# 2_0.net
KiCad netlist of a schematic drawn in Altium Designer
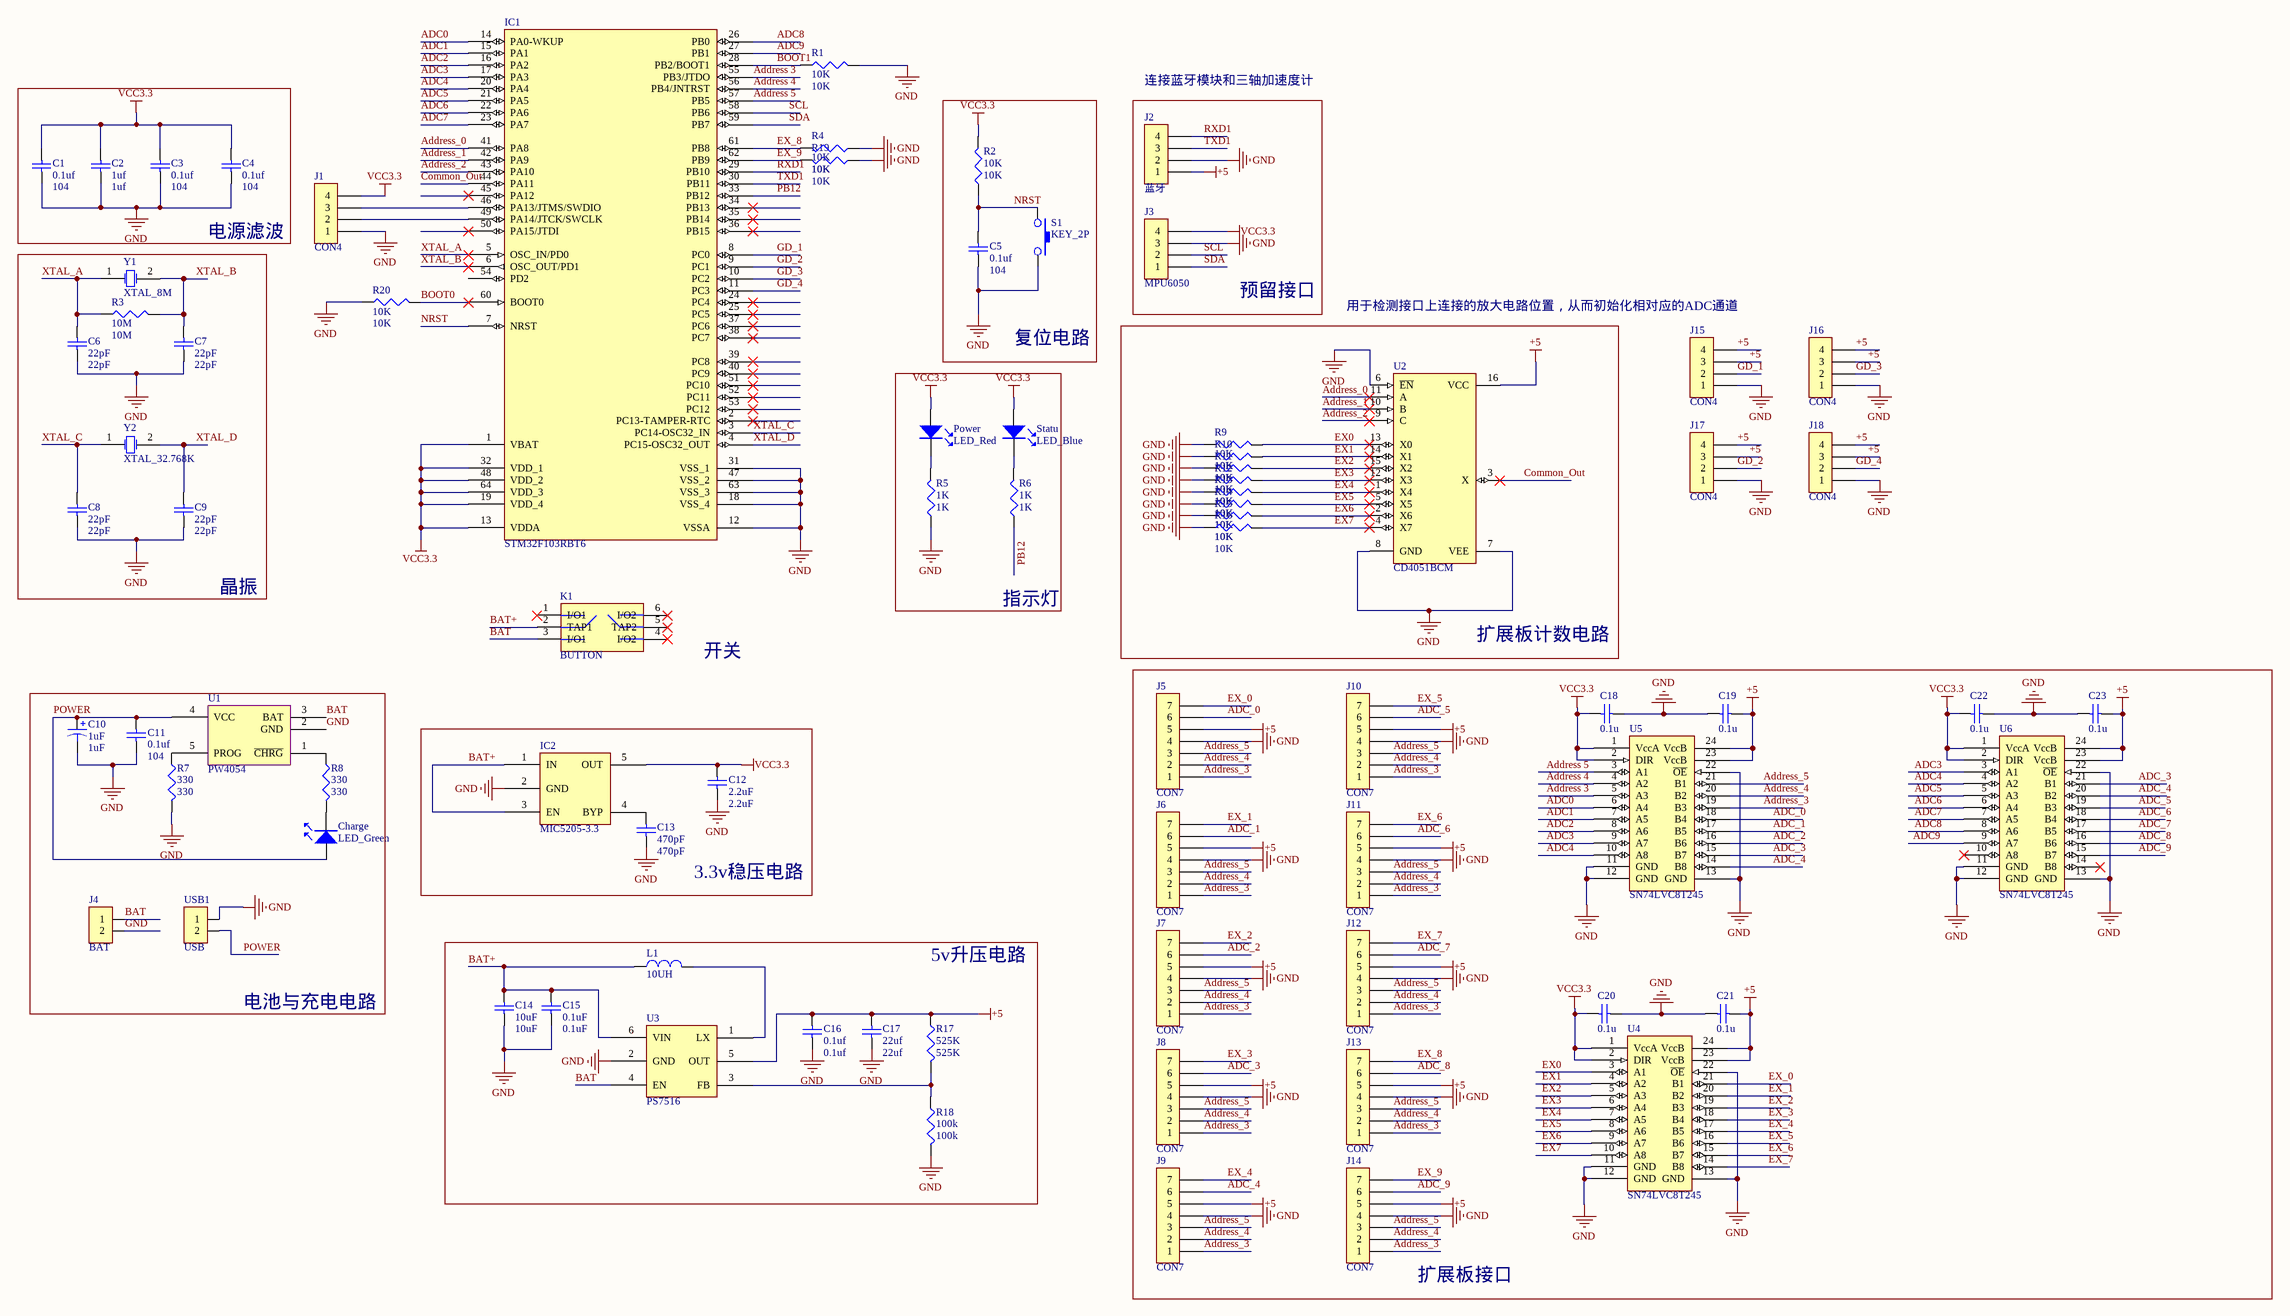
[diagram p0: 主控板原理图2.0.SchDoc]

(export (version "E")
  (design (tool "Eeschema 10.0.6"))
  (components
    (comp (ref "C1")
      (value "0.1uf")
      (footprint "6-0805_L")
      (description "Capacitor (Semiconductor SIM Model)")
      (fields (field (name "ALTIUM_VALUE") "104") (field (name "PUBLISHER") "Altium Limited"))
      (libsource (lib "Miscellaneous Devices") (part "Cap Semi"))
    )
    (comp (ref "C2")
      (value "1uf")
      (footprint "6-0805_L")
      (description "Capacitor (Semiconductor SIM Model)")
      (fields (field (name "ALTIUM_VALUE") "1uf") (field (name "PUBLISHER") "Altium Limited"))
      (libsource (lib "Miscellaneous Devices") (part "Cap Semi"))
    )
    (comp (ref "C3")
      (value "0.1uf")
      (footprint "6-0805_L")
      (description "Capacitor (Semiconductor SIM Model)")
      (fields (field (name "ALTIUM_VALUE") "104") (field (name "PUBLISHER") "Altium Limited"))
      (libsource (lib "Miscellaneous Devices") (part "Cap Semi"))
    )
    (comp (ref "C4")
      (value "0.1uf")
      (footprint "6-0805_L")
      (description "Capacitor (Semiconductor SIM Model)")
      (fields (field (name "ALTIUM_VALUE") "104") (field (name "PUBLISHER") "Altium Limited"))
      (libsource (lib "Miscellaneous Devices") (part "Cap Semi"))
    )
    (comp (ref "C5")
      (value "0.1uf")
      (footprint "6-0805_L")
      (description "Capacitor (Semiconductor SIM Model)")
      (fields (field (name "ALTIUM_VALUE") "104") (field (name "PUBLISHER") "Altium Limited"))
      (libsource (lib "Miscellaneous Devices") (part "Cap Semi"))
    )
    (comp (ref "C6")
      (value "22pF")
      (footprint "6-0805_L")
      (description "Capacitor (Semiconductor SIM Model)")
      (fields (field (name "ALTIUM_VALUE") "22pF") (field (name "PUBLISHER") "Altium Limited"))
      (libsource (lib "Miscellaneous Devices") (part "Cap Semi"))
    )
    (comp (ref "C7")
      (value "22pF")
      (footprint "6-0805_L")
      (description "Capacitor (Semiconductor SIM Model)")
      (fields (field (name "ALTIUM_VALUE") "22pF") (field (name "PUBLISHER") "Altium Limited"))
      (libsource (lib "Miscellaneous Devices") (part "Cap Semi"))
    )
    (comp (ref "C8")
      (value "22pF")
      (footprint "6-0805_L")
      (description "Capacitor (Semiconductor SIM Model)")
      (fields (field (name "ALTIUM_VALUE") "22pF") (field (name "PUBLISHER") "Altium Limited"))
      (libsource (lib "Miscellaneous Devices") (part "Cap Semi"))
    )
    (comp (ref "C9")
      (value "22pF")
      (footprint "6-0805_L")
      (description "Capacitor (Semiconductor SIM Model)")
      (fields (field (name "ALTIUM_VALUE") "22pF") (field (name "PUBLISHER") "Altium Limited"))
      (libsource (lib "Miscellaneous Devices") (part "Cap Semi"))
    )
    (comp (ref "C10")
      (value "1uF")
      (footprint "C0805")
      (description "Polarized Capacitor (Surface Mount)")
      (fields (field (name "ALTIUM_VALUE") "1uF") (field (name "PUBLISHER") "Altium Limited"))
      (libsource (lib "Miscellaneous Devices") (part "Cap Pol3"))
    )
    (comp (ref "C11")
      (value "0.1uf")
      (footprint "6-0805_L")
      (description "Capacitor (Semiconductor SIM Model)")
      (fields (field (name "ALTIUM_VALUE") "104") (field (name "PUBLISHER") "Altium Limited"))
      (libsource (lib "Miscellaneous Devices") (part "Cap Semi"))
    )
    (comp (ref "C12")
      (value "2.2uF")
      (footprint "6-0805_L")
      (description "Capacitor (Semiconductor SIM Model)")
      (fields (field (name "ALTIUM_VALUE") "2.2uF") (field (name "PUBLISHER") "Altium Limited"))
      (libsource (lib "Miscellaneous Devices") (part "Cap Semi"))
    )
    (comp (ref "C13")
      (value "470pF")
      (footprint "6-0805_L")
      (description "Capacitor (Semiconductor SIM Model)")
      (fields (field (name "ALTIUM_VALUE") "470pF") (field (name "PUBLISHER") "Altium Limited"))
      (libsource (lib "Miscellaneous Devices") (part "Cap Semi"))
    )
    (comp (ref "C14")
      (value "10uF")
      (footprint "6-0805_L")
      (description "Capacitor (Semiconductor SIM Model)")
      (fields (field (name "ALTIUM_VALUE") "10uF") (field (name "PUBLISHER") "Altium Limited"))
      (libsource (lib "Miscellaneous Devices") (part "Cap Semi"))
    )
    (comp (ref "C15")
      (value "0.1uF")
      (footprint "6-0805_L")
      (description "Capacitor (Semiconductor SIM Model)")
      (fields (field (name "ALTIUM_VALUE") "0.1uF") (field (name "PUBLISHER") "Altium Limited"))
      (libsource (lib "Miscellaneous Devices") (part "Cap Semi"))
    )
    (comp (ref "C16")
      (value "0.1uf")
      (footprint "6-0805_L")
      (description "Capacitor (Semiconductor SIM Model)")
      (fields (field (name "ALTIUM_VALUE") "0.1uf") (field (name "PUBLISHER") "Altium Limited"))
      (libsource (lib "Miscellaneous Devices") (part "Cap Semi"))
    )
    (comp (ref "C17")
      (value "22uf")
      (footprint "6-0805_L")
      (description "Capacitor (Semiconductor SIM Model)")
      (fields (field (name "ALTIUM_VALUE") "22uf") (field (name "PUBLISHER") "Altium Limited"))
      (libsource (lib "Miscellaneous Devices") (part "Cap Semi"))
    )
    (comp (ref "C18")
      (value "0.1u")
      (footprint "CAP1608")
      (description "Capacitor")
      (fields (field (name "Comment") "Cap") (field (name "PUBLISHER") "Altium Limited"))
      (libsource (lib "Miscellaneous Devices") (part "Cap"))
    )
    (comp (ref "C19")
      (value "0.1u")
      (footprint "CAP1608")
      (description "Capacitor")
      (fields (field (name "Comment") "Cap") (field (name "PUBLISHER") "Altium Limited"))
      (libsource (lib "Miscellaneous Devices") (part "Cap"))
    )
    (comp (ref "C20")
      (value "0.1u")
      (footprint "CAP1608")
      (description "Capacitor")
      (fields (field (name "Comment") "Cap") (field (name "PUBLISHER") "Altium Limited"))
      (libsource (lib "Miscellaneous Devices") (part "Cap"))
    )
    (comp (ref "C21")
      (value "0.1u")
      (footprint "CAP1608")
      (description "Capacitor")
      (fields (field (name "Comment") "Cap") (field (name "PUBLISHER") "Altium Limited"))
      (libsource (lib "Miscellaneous Devices") (part "Cap"))
    )
    (comp (ref "C22")
      (value "0.1u")
      (footprint "CAP1608")
      (description "Capacitor")
      (fields (field (name "Comment") "Cap") (field (name "PUBLISHER") "Altium Limited"))
      (libsource (lib "Miscellaneous Devices") (part "Cap"))
    )
    (comp (ref "C23")
      (value "0.1u")
      (footprint "CAP1608")
      (description "Capacitor")
      (fields (field (name "Comment") "Cap") (field (name "PUBLISHER") "Altium Limited"))
      (libsource (lib "Miscellaneous Devices") (part "Cap"))
    )
    (comp (ref "Charge")
      (value "LED_Green")
      (footprint "6-0805_M")
      (description "LED")
      (libsource (lib "Component") (part "LED"))
    )
    (comp (ref "IC1")
      (value "STM32F103RBT6")
      (footprint "LQFP64_N")
      (description "STM32 ARM-based 32-bit MCU with 128 Kbytes Flash, 64-pin LQFP, Industrial Temperature")
      (fields (field (name "PUBLISHER") "Altium Limited"))
      (libsource (lib "ST Microcontroller 32-Bit STM32") (part "STM32F103RBT6"))
    )
    (comp (ref "IC2")
      (value "MIC5205-3.3")
      (footprint "SOT-23-5")
      (description "稳压")
      (libsource (lib "Chip") (part "MIC5205-3.3"))
    )
    (comp (ref "J1")
      (value "CON4")
      (footprint "HDR1X4")
      (description "连接器")
      (libsource (lib "Connector") (part "CON4"))
    )
    (comp (ref "J2")
      (value "蓝牙")
      (footprint "HDR1X4")
      (description "Connector")
      (libsource (lib "杂元件库") (part "CON4"))
    )
    (comp (ref "J3")
      (value "MPU6050")
      (footprint "HDR1X4")
      (description "Connector")
      (libsource (lib "杂元件库") (part "CON4"))
    )
    (comp (ref "J4")
      (value "BAT")
      (footprint "HDR1X2")
      (description "Conjunctor")
      (libsource (lib "zj") (part "CON2"))
    )
    (comp (ref "J5")
      (value "CON7")
      (footprint "8P软排线")
      (description "Connector")
      (libsource (lib "杂元件库") (part "CON7"))
    )
    (comp (ref "J6")
      (value "CON7")
      (footprint "8P软排线")
      (description "Connector")
      (libsource (lib "杂元件库") (part "CON7"))
    )
    (comp (ref "J7")
      (value "CON7")
      (footprint "8P软排线")
      (description "Connector")
      (libsource (lib "杂元件库") (part "CON7"))
    )
    (comp (ref "J8")
      (value "CON7")
      (footprint "8P软排线")
      (description "Connector")
      (libsource (lib "杂元件库") (part "CON7"))
    )
    (comp (ref "J9")
      (value "CON7")
      (footprint "8P软排线")
      (description "Connector")
      (libsource (lib "杂元件库") (part "CON7"))
    )
    (comp (ref "J10")
      (value "CON7")
      (footprint "8P软排线")
      (description "Connector")
      (libsource (lib "杂元件库") (part "CON7"))
    )
    (comp (ref "J11")
      (value "CON7")
      (footprint "8P软排线")
      (description "Connector")
      (libsource (lib "杂元件库") (part "CON7"))
    )
    (comp (ref "J12")
      (value "CON7")
      (footprint "8P软排线")
      (description "Connector")
      (libsource (lib "杂元件库") (part "CON7"))
    )
    (comp (ref "J13")
      (value "CON7")
      (footprint "8P软排线")
      (description "Connector")
      (libsource (lib "杂元件库") (part "CON7"))
    )
    (comp (ref "J14")
      (value "CON7")
      (footprint "8P软排线")
      (description "Connector")
      (libsource (lib "杂元件库") (part "CON7"))
    )
    (comp (ref "J15")
      (value "CON4")
      (footprint "软排线4p")
      (description "Connector")
      (libsource (lib "杂元件库") (part "CON4"))
    )
    (comp (ref "J16")
      (value "CON4")
      (footprint "软排线4p")
      (description "Connector")
      (libsource (lib "杂元件库") (part "CON4"))
    )
    (comp (ref "J17")
      (value "CON4")
      (footprint "软排线4p")
      (description "Connector")
      (libsource (lib "杂元件库") (part "CON4"))
    )
    (comp (ref "J18")
      (value "CON4")
      (footprint "软排线4p")
      (description "Connector")
      (libsource (lib "杂元件库") (part "CON4"))
    )
    (comp (ref "K1")
      (value "BUTTON")
      (footprint "My:switch")
      (description "自锁按键")
      (libsource (lib "Component") (part "BUTTON"))
    )
    (comp (ref "L1")
      (value "10UH")
      (footprint "0850")
      (description "电感")
      (libsource (lib "Component") (part "Inductor"))
    )
    (comp (ref "Power")
      (value "LED_Red")
      (footprint "6-0805_M")
      (description "LED")
      (libsource (lib "Component") (part "LED"))
    )
    (comp (ref "R1")
      (value "10K")
      (footprint "6-0805_L")
      (description "Resistor")
      (fields (field (name "ALTIUM_VALUE") "10K") (field (name "PUBLISHER") "Altium Limited"))
      (libsource (lib "Miscellaneous Devices") (part "Res3"))
    )
    (comp (ref "R2")
      (value "10K")
      (footprint "6-0805_L")
      (description "Resistor")
      (fields (field (name "ALTIUM_VALUE") "10K") (field (name "PUBLISHER") "Altium Limited"))
      (libsource (lib "Miscellaneous Devices") (part "Res3"))
    )
    (comp (ref "R3")
      (value "10M")
      (footprint "6-0805_L")
      (description "Resistor")
      (fields (field (name "ALTIUM_VALUE") "10M") (field (name "PUBLISHER") "Altium Limited"))
      (libsource (lib "Miscellaneous Devices") (part "Res3"))
    )
    (comp (ref "R4")
      (value "10K")
      (footprint "6-0805_L")
      (description "Resistor")
      (fields (field (name "ALTIUM_VALUE") "10K") (field (name "PUBLISHER") "Altium Limited"))
      (libsource (lib "Miscellaneous Devices") (part "Res3"))
    )
    (comp (ref "R5")
      (value "1K")
      (footprint "6-0805_L")
      (description "Resistor")
      (fields (field (name "ALTIUM_VALUE") "1K") (field (name "PUBLISHER") "Altium Limited"))
      (libsource (lib "Miscellaneous Devices") (part "Res3"))
    )
    (comp (ref "R6")
      (value "1K")
      (footprint "6-0805_L")
      (description "Resistor")
      (fields (field (name "ALTIUM_VALUE") "1K") (field (name "PUBLISHER") "Altium Limited"))
      (libsource (lib "Miscellaneous Devices") (part "Res3"))
    )
    (comp (ref "R7")
      (value "330")
      (footprint "6-0805_L")
      (description "Resistor")
      (fields (field (name "ALTIUM_VALUE") "330") (field (name "PUBLISHER") "Altium Limited"))
      (libsource (lib "Miscellaneous Devices") (part "Res3"))
    )
    (comp (ref "R8")
      (value "330")
      (footprint "6-0805_L")
      (description "Resistor")
      (fields (field (name "ALTIUM_VALUE") "330") (field (name "PUBLISHER") "Altium Limited"))
      (libsource (lib "Miscellaneous Devices") (part "Res3"))
    )
    (comp (ref "R9")
      (value "10K")
      (footprint "6-0805_L")
      (description "Resistor")
      (fields (field (name "ALTIUM_VALUE") "10K") (field (name "PUBLISHER") "Altium Limited"))
      (libsource (lib "Miscellaneous Devices") (part "Res3"))
    )
    (comp (ref "R10")
      (value "10K")
      (footprint "6-0805_L")
      (description "Resistor")
      (fields (field (name "ALTIUM_VALUE") "10K") (field (name "PUBLISHER") "Altium Limited"))
      (libsource (lib "Miscellaneous Devices") (part "Res3"))
    )
    (comp (ref "R11")
      (value "10K")
      (footprint "6-0805_L")
      (description "Resistor")
      (fields (field (name "ALTIUM_VALUE") "10K") (field (name "PUBLISHER") "Altium Limited"))
      (libsource (lib "Miscellaneous Devices") (part "Res3"))
    )
    (comp (ref "R12")
      (value "10K")
      (footprint "6-0805_L")
      (description "Resistor")
      (fields (field (name "ALTIUM_VALUE") "10K") (field (name "PUBLISHER") "Altium Limited"))
      (libsource (lib "Miscellaneous Devices") (part "Res3"))
    )
    (comp (ref "R13")
      (value "10K")
      (footprint "6-0805_L")
      (description "Resistor")
      (fields (field (name "ALTIUM_VALUE") "10K") (field (name "PUBLISHER") "Altium Limited"))
      (libsource (lib "Miscellaneous Devices") (part "Res3"))
    )
    (comp (ref "R14")
      (value "10K")
      (footprint "6-0805_L")
      (description "Resistor")
      (fields (field (name "ALTIUM_VALUE") "10K") (field (name "PUBLISHER") "Altium Limited"))
      (libsource (lib "Miscellaneous Devices") (part "Res3"))
    )
    (comp (ref "R15")
      (value "10K")
      (footprint "6-0805_L")
      (description "Resistor")
      (fields (field (name "ALTIUM_VALUE") "10K") (field (name "PUBLISHER") "Altium Limited"))
      (libsource (lib "Miscellaneous Devices") (part "Res3"))
    )
    (comp (ref "R16")
      (value "10K")
      (footprint "6-0805_L")
      (description "Resistor")
      (fields (field (name "ALTIUM_VALUE") "10K") (field (name "PUBLISHER") "Altium Limited"))
      (libsource (lib "Miscellaneous Devices") (part "Res3"))
    )
    (comp (ref "R17")
      (value "525K")
      (footprint "6-0805_L")
      (description "Resistor")
      (fields (field (name "ALTIUM_VALUE") "525K") (field (name "PUBLISHER") "Altium Limited"))
      (libsource (lib "Miscellaneous Devices") (part "Res3"))
    )
    (comp (ref "R18")
      (value "100k")
      (footprint "6-0805_L")
      (description "Resistor")
      (fields (field (name "ALTIUM_VALUE") "100k") (field (name "PUBLISHER") "Altium Limited"))
      (libsource (lib "Miscellaneous Devices") (part "Res3"))
    )
    (comp (ref "R19")
      (value "10K")
      (footprint "6-0805_L")
      (description "Resistor")
      (fields (field (name "ALTIUM_VALUE") "10K") (field (name "PUBLISHER") "Altium Limited"))
      (libsource (lib "Miscellaneous Devices") (part "Res3"))
    )
    (comp (ref "R20")
      (value "10K")
      (footprint "6-0805_L")
      (description "Resistor")
      (fields (field (name "ALTIUM_VALUE") "10K") (field (name "PUBLISHER") "Altium Limited"))
      (libsource (lib "Miscellaneous Devices") (part "Res3"))
    )
    (comp (ref "S1")
      (value "KEY_2P")
      (footprint "My:button")
      (description "轻触按键2P")
      (libsource (lib "Component") (part "KEY_2P"))
    )
    (comp (ref "Statu")
      (value "LED_Blue")
      (footprint "6-0805_M")
      (description "LED")
      (libsource (lib "Component") (part "LED"))
    )
    (comp (ref "U1") (value "PW4054") (footprint "SOT-23-CT5_L") (libsource (lib "Schlib") (part "PW4054")))
    (comp (ref "U2")
      (value "CD4051BCM")
      (footprint "M16A_N")
      (description "8-Channel Analog Multiplexer/Demultiplexer")
      (fields (field (name "PUBLISHER") "Altium Limited"))
      (libsource (lib "altium-import") (part "root_0_CD4051BCM_"))
    )
    (comp (ref "U3")
      (value "PS7516")
      (footprint "SOT23-6_M")
      (libsource (lib "Integrated_Library1") (part "PS7516"))
    )
    (comp (ref "U4")
      (value "SN74LVC8T245")
      (footprint "SN74LVC8T245")
      (libsource (lib "Schlib1zhu") (part "SN74LVC8T245"))
    )
    (comp (ref "U5")
      (value "SN74LVC8T245")
      (footprint "SN74LVC8T245")
      (libsource (lib "Schlib1zhu") (part "SN74LVC8T245"))
    )
    (comp (ref "U6")
      (value "SN74LVC8T245")
      (footprint "SN74LVC8T245")
      (libsource (lib "Schlib1zhu") (part "SN74LVC8T245"))
    )
    (comp (ref "USB1")
      (value "USB")
      (footprint "Type-C")
      (description "Conjunctor")
      (libsource (lib "zj") (part "CON2"))
    )
    (comp (ref "Y1")
      (value "XTAL_8M")
      (footprint "xtal")
      (description "Crystal Oscillator")
      (fields (field (name "PUBLISHER") "Altium Limited"))
      (libsource (lib "Miscellaneous Devices") (part "XTAL"))
    )
    (comp (ref "Y2")
      (value "XTAL_32.768K")
      (footprint "R38")
      (description "Crystal Oscillator")
      (fields (field (name "PUBLISHER") "Altium Limited"))
      (libsource (lib "Miscellaneous Devices") (part "XTAL"))
    )
  )
  (nets
    (net (code "1") (name "+5") (class "Default")
      (node (ref "C16") (pin "2") (pinfunction "2_2") (pintype "passive"))
      (node (ref "C17") (pin "2") (pinfunction "2_2") (pintype "passive"))
      (node (ref "C19") (pin "1") (pinfunction "1_1") (pintype "passive"))
      (node (ref "C21") (pin "1") (pinfunction "1_1") (pintype "passive"))
      (node (ref "C23") (pin "1") (pinfunction "1_1") (pintype "passive"))
      (node (ref "J10") (pin "5") (pinfunction "5_5") (pintype "passive"))
      (node (ref "J11") (pin "5") (pinfunction "5_5") (pintype "passive"))
      (node (ref "J12") (pin "5") (pinfunction "5_5") (pintype "passive"))
      (node (ref "J13") (pin "5") (pinfunction "5_5") (pintype "passive"))
      (node (ref "J14") (pin "5") (pinfunction "5_5") (pintype "passive"))
      (node (ref "J15") (pin "3") (pinfunction "3_3") (pintype "passive"))
      (node (ref "J15") (pin "4") (pinfunction "4_4") (pintype "passive"))
      (node (ref "J16") (pin "3") (pinfunction "3_3") (pintype "passive"))
      (node (ref "J16") (pin "4") (pinfunction "4_4") (pintype "passive"))
      (node (ref "J17") (pin "3") (pinfunction "3_3") (pintype "passive"))
      (node (ref "J17") (pin "4") (pinfunction "4_4") (pintype "passive"))
      (node (ref "J18") (pin "3") (pinfunction "3_3") (pintype "passive"))
      (node (ref "J18") (pin "4") (pinfunction "4_4") (pintype "passive"))
      (node (ref "J2") (pin "1") (pinfunction "1_1") (pintype "passive"))
      (node (ref "J5") (pin "5") (pinfunction "5_5") (pintype "passive"))
      (node (ref "J6") (pin "5") (pinfunction "5_5") (pintype "passive"))
      (node (ref "J7") (pin "5") (pinfunction "5_5") (pintype "passive"))
      (node (ref "J8") (pin "5") (pinfunction "5_5") (pintype "passive"))
      (node (ref "J9") (pin "5") (pinfunction "5_5") (pintype "passive"))
      (node (ref "R17") (pin "1") (pinfunction "1_1") (pintype "passive"))
      (node (ref "U2") (pin "16") (pinfunction "VCC_16") (pintype "power_in"))
      (node (ref "U3") (pin "5") (pinfunction "OUT_5") (pintype "passive"))
      (node (ref "U4") (pin "23") (pinfunction "VccB_23") (pintype "power_in"))
      (node (ref "U4") (pin "24") (pinfunction "VccB_24") (pintype "power_in"))
      (node (ref "U5") (pin "23") (pinfunction "VccB_23") (pintype "power_in"))
      (node (ref "U5") (pin "24") (pinfunction "VccB_24") (pintype "power_in"))
      (node (ref "U6") (pin "23") (pinfunction "VccB_23") (pintype "power_in"))
      (node (ref "U6") (pin "24") (pinfunction "VccB_24") (pintype "power_in"))
    )
    (net (code "2") (name "/ADC0") (class "Default")
      (node (ref "IC1") (pin "14") (pinfunction "PA0-WKUP_14") (pintype "bidirectional"))
      (node (ref "U5") (pin "6") (pinfunction "A4_6") (pintype "bidirectional"))
    )
    (net (code "3") (name "/ADC1") (class "Default")
      (node (ref "IC1") (pin "15") (pinfunction "PA1_15") (pintype "bidirectional"))
      (node (ref "U5") (pin "7") (pinfunction "A5_7") (pintype "bidirectional"))
    )
    (net (code "4") (name "/ADC2") (class "Default")
      (node (ref "IC1") (pin "16") (pinfunction "PA2_16") (pintype "bidirectional"))
      (node (ref "U5") (pin "8") (pinfunction "A6_8") (pintype "bidirectional"))
    )
    (net (code "5") (name "/ADC3") (class "Default")
      (node (ref "IC1") (pin "17") (pinfunction "PA3_17") (pintype "bidirectional"))
      (node (ref "U5") (pin "9") (pinfunction "A7_9") (pintype "bidirectional"))
      (node (ref "U6") (pin "3") (pinfunction "A1_3") (pintype "bidirectional"))
    )
    (net (code "6") (name "/ADC4") (class "Default")
      (node (ref "IC1") (pin "20") (pinfunction "PA4_20") (pintype "bidirectional"))
      (node (ref "U5") (pin "10") (pinfunction "A8_10") (pintype "bidirectional"))
      (node (ref "U6") (pin "4") (pinfunction "A2_4") (pintype "bidirectional"))
    )
    (net (code "7") (name "/ADC5") (class "Default")
      (node (ref "IC1") (pin "21") (pinfunction "PA5_21") (pintype "bidirectional"))
      (node (ref "U6") (pin "5") (pinfunction "A3_5") (pintype "bidirectional"))
    )
    (net (code "8") (name "/ADC6") (class "Default")
      (node (ref "IC1") (pin "22") (pinfunction "PA6_22") (pintype "bidirectional"))
      (node (ref "U6") (pin "6") (pinfunction "A4_6") (pintype "bidirectional"))
    )
    (net (code "9") (name "/ADC7") (class "Default")
      (node (ref "IC1") (pin "23") (pinfunction "PA7_23") (pintype "bidirectional"))
      (node (ref "U6") (pin "7") (pinfunction "A5_7") (pintype "bidirectional"))
    )
    (net (code "10") (name "/ADC8") (class "Default")
      (node (ref "IC1") (pin "26") (pinfunction "PB0_26") (pintype "bidirectional"))
      (node (ref "U6") (pin "8") (pinfunction "A6_8") (pintype "bidirectional"))
    )
    (net (code "11") (name "/ADC9") (class "Default")
      (node (ref "IC1") (pin "27") (pinfunction "PB1_27") (pintype "bidirectional"))
      (node (ref "U6") (pin "9") (pinfunction "A7_9") (pintype "bidirectional"))
    )
    (net (code "12") (name "/ADC_0") (class "Default")
      (node (ref "J5") (pin "6") (pinfunction "6_6") (pintype "passive"))
      (node (ref "U5") (pin "18") (pinfunction "B4_18") (pintype "bidirectional"))
    )
    (net (code "13") (name "/ADC_1") (class "Default")
      (node (ref "J6") (pin "6") (pinfunction "6_6") (pintype "passive"))
      (node (ref "U5") (pin "17") (pinfunction "B5_17") (pintype "bidirectional"))
    )
    (net (code "14") (name "/ADC_2") (class "Default")
      (node (ref "J7") (pin "6") (pinfunction "6_6") (pintype "passive"))
      (node (ref "U5") (pin "16") (pinfunction "B6_16") (pintype "bidirectional"))
    )
    (net (code "15") (name "/ADC_3") (class "Default")
      (node (ref "J8") (pin "6") (pinfunction "6_6") (pintype "passive"))
      (node (ref "U5") (pin "15") (pinfunction "B7_15") (pintype "bidirectional"))
      (node (ref "U6") (pin "21") (pinfunction "B1_21") (pintype "bidirectional"))
    )
    (net (code "16") (name "/ADC_4") (class "Default")
      (node (ref "J9") (pin "6") (pinfunction "6_6") (pintype "passive"))
      (node (ref "U5") (pin "14") (pinfunction "B8_14") (pintype "bidirectional"))
      (node (ref "U6") (pin "20") (pinfunction "B2_20") (pintype "bidirectional"))
    )
    (net (code "17") (name "/ADC_5") (class "Default")
      (node (ref "J10") (pin "6") (pinfunction "6_6") (pintype "passive"))
      (node (ref "U6") (pin "19") (pinfunction "B3_19") (pintype "bidirectional"))
    )
    (net (code "18") (name "/ADC_6") (class "Default")
      (node (ref "J11") (pin "6") (pinfunction "6_6") (pintype "passive"))
      (node (ref "U6") (pin "18") (pinfunction "B4_18") (pintype "bidirectional"))
    )
    (net (code "19") (name "/ADC_7") (class "Default")
      (node (ref "J12") (pin "6") (pinfunction "6_6") (pintype "passive"))
      (node (ref "U6") (pin "17") (pinfunction "B5_17") (pintype "bidirectional"))
    )
    (net (code "20") (name "/ADC_8") (class "Default")
      (node (ref "J13") (pin "6") (pinfunction "6_6") (pintype "passive"))
      (node (ref "U6") (pin "16") (pinfunction "B6_16") (pintype "bidirectional"))
    )
    (net (code "21") (name "/ADC_9") (class "Default")
      (node (ref "J14") (pin "6") (pinfunction "6_6") (pintype "passive"))
      (node (ref "U6") (pin "15") (pinfunction "B7_15") (pintype "bidirectional"))
    )
    (net (code "22") (name "/Address 3") (class "Default")
      (node (ref "IC1") (pin "55") (pinfunction "PB3/JTDO_55") (pintype "bidirectional"))
      (node (ref "U5") (pin "5") (pinfunction "A3_5") (pintype "bidirectional"))
    )
    (net (code "23") (name "/Address 4") (class "Default")
      (node (ref "IC1") (pin "56") (pinfunction "PB4/JNTRST_56") (pintype "bidirectional"))
      (node (ref "U5") (pin "4") (pinfunction "A2_4") (pintype "bidirectional"))
    )
    (net (code "24") (name "/Address 5") (class "Default")
      (node (ref "IC1") (pin "57") (pinfunction "PB5_57") (pintype "bidirectional"))
      (node (ref "U5") (pin "3") (pinfunction "A1_3") (pintype "bidirectional"))
    )
    (net (code "25") (name "/Address_0") (class "Default")
      (node (ref "IC1") (pin "41") (pinfunction "PA8_41") (pintype "bidirectional"))
      (node (ref "U2") (pin "11") (pinfunction "A_11") (pintype "input"))
    )
    (net (code "26") (name "/Address_1") (class "Default")
      (node (ref "IC1") (pin "42") (pinfunction "PA9_42") (pintype "bidirectional"))
      (node (ref "U2") (pin "10") (pinfunction "B_10") (pintype "input"))
    )
    (net (code "27") (name "/Address_2") (class "Default")
      (node (ref "IC1") (pin "43") (pinfunction "PA10_43") (pintype "bidirectional"))
      (node (ref "U2") (pin "9") (pinfunction "C_9") (pintype "input"))
    )
    (net (code "28") (name "/Address_3") (class "Default")
      (node (ref "J10") (pin "1") (pinfunction "1_1") (pintype "passive"))
      (node (ref "J11") (pin "1") (pinfunction "1_1") (pintype "passive"))
      (node (ref "J12") (pin "1") (pinfunction "1_1") (pintype "passive"))
      (node (ref "J13") (pin "1") (pinfunction "1_1") (pintype "passive"))
      (node (ref "J14") (pin "1") (pinfunction "1_1") (pintype "passive"))
      (node (ref "J5") (pin "1") (pinfunction "1_1") (pintype "passive"))
      (node (ref "J6") (pin "1") (pinfunction "1_1") (pintype "passive"))
      (node (ref "J7") (pin "1") (pinfunction "1_1") (pintype "passive"))
      (node (ref "J8") (pin "1") (pinfunction "1_1") (pintype "passive"))
      (node (ref "J9") (pin "1") (pinfunction "1_1") (pintype "passive"))
      (node (ref "U5") (pin "19") (pinfunction "B3_19") (pintype "bidirectional"))
    )
    (net (code "29") (name "/Address_4") (class "Default")
      (node (ref "J10") (pin "2") (pinfunction "2_2") (pintype "passive"))
      (node (ref "J11") (pin "2") (pinfunction "2_2") (pintype "passive"))
      (node (ref "J12") (pin "2") (pinfunction "2_2") (pintype "passive"))
      (node (ref "J13") (pin "2") (pinfunction "2_2") (pintype "passive"))
      (node (ref "J14") (pin "2") (pinfunction "2_2") (pintype "passive"))
      (node (ref "J5") (pin "2") (pinfunction "2_2") (pintype "passive"))
      (node (ref "J6") (pin "2") (pinfunction "2_2") (pintype "passive"))
      (node (ref "J7") (pin "2") (pinfunction "2_2") (pintype "passive"))
      (node (ref "J8") (pin "2") (pinfunction "2_2") (pintype "passive"))
      (node (ref "J9") (pin "2") (pinfunction "2_2") (pintype "passive"))
      (node (ref "U5") (pin "20") (pinfunction "B2_20") (pintype "bidirectional"))
    )
    (net (code "30") (name "/Address_5") (class "Default")
      (node (ref "J10") (pin "3") (pinfunction "3_3") (pintype "passive"))
      (node (ref "J11") (pin "3") (pinfunction "3_3") (pintype "passive"))
      (node (ref "J12") (pin "3") (pinfunction "3_3") (pintype "passive"))
      (node (ref "J13") (pin "3") (pinfunction "3_3") (pintype "passive"))
      (node (ref "J14") (pin "3") (pinfunction "3_3") (pintype "passive"))
      (node (ref "J5") (pin "3") (pinfunction "3_3") (pintype "passive"))
      (node (ref "J6") (pin "3") (pinfunction "3_3") (pintype "passive"))
      (node (ref "J7") (pin "3") (pinfunction "3_3") (pintype "passive"))
      (node (ref "J8") (pin "3") (pinfunction "3_3") (pintype "passive"))
      (node (ref "J9") (pin "3") (pinfunction "3_3") (pintype "passive"))
      (node (ref "U5") (pin "21") (pinfunction "B1_21") (pintype "bidirectional"))
    )
    (net (code "31") (name "/BAT") (class "Default")
      (node (ref "J4") (pin "1") (pinfunction "1_1") (pintype "passive"))
      (node (ref "K1") (pin "3") (pinfunction "I/O1_3") (pintype "passive"))
      (node (ref "U1") (pin "3") (pinfunction "BAT_3") (pintype "passive"))
      (node (ref "U3") (pin "4") (pinfunction "EN_4") (pintype "passive"))
    )
    (net (code "32") (name "/BAT+") (class "Default")
      (node (ref "C14") (pin "2") (pinfunction "2_2") (pintype "passive"))
      (node (ref "C15") (pin "2") (pinfunction "2_2") (pintype "passive"))
      (node (ref "IC2") (pin "1") (pinfunction "IN_1") (pintype "passive"))
      (node (ref "IC2") (pin "3") (pinfunction "EN_3") (pintype "passive"))
      (node (ref "K1") (pin "2") (pinfunction "TAP1_2") (pintype "passive"))
      (node (ref "L1") (pin "1") (pinfunction "1_1") (pintype "passive"))
      (node (ref "U3") (pin "6") (pinfunction "VIN_6") (pintype "passive"))
    )
    (net (code "33") (name "/BOOT0") (class "Default")
      (node (ref "IC1") (pin "60") (pinfunction "BOOT0_60") (pintype "input"))
      (node (ref "R20") (pin "2") (pinfunction "2_2") (pintype "passive"))
    )
    (net (code "34") (name "/BOOT1") (class "Default")
      (node (ref "IC1") (pin "28") (pinfunction "PB2/BOOT1_28") (pintype "bidirectional"))
      (node (ref "R1") (pin "1") (pinfunction "1_1") (pintype "passive"))
    )
    (net (code "35") (name "/Common_Out") (class "Default")
      (node (ref "IC1") (pin "44") (pinfunction "PA11_44") (pintype "bidirectional"))
      (node (ref "U2") (pin "3") (pinfunction "X_3") (pintype "bidirectional"))
    )
    (net (code "36") (name "/EX0") (class "Default")
      (node (ref "R9") (pin "2") (pinfunction "2_2") (pintype "passive"))
      (node (ref "U2") (pin "13") (pinfunction "X0_13") (pintype "bidirectional"))
      (node (ref "U4") (pin "3") (pinfunction "A1_3") (pintype "bidirectional"))
    )
    (net (code "37") (name "/EX1") (class "Default")
      (node (ref "R10") (pin "2") (pinfunction "2_2") (pintype "passive"))
      (node (ref "U2") (pin "14") (pinfunction "X1_14") (pintype "bidirectional"))
      (node (ref "U4") (pin "4") (pinfunction "A2_4") (pintype "bidirectional"))
    )
    (net (code "38") (name "/EX2") (class "Default")
      (node (ref "R11") (pin "2") (pinfunction "2_2") (pintype "passive"))
      (node (ref "U2") (pin "15") (pinfunction "X2_15") (pintype "bidirectional"))
      (node (ref "U4") (pin "5") (pinfunction "A3_5") (pintype "bidirectional"))
    )
    (net (code "39") (name "/EX3") (class "Default")
      (node (ref "R12") (pin "2") (pinfunction "2_2") (pintype "passive"))
      (node (ref "U2") (pin "12") (pinfunction "X3_12") (pintype "bidirectional"))
      (node (ref "U4") (pin "6") (pinfunction "A4_6") (pintype "bidirectional"))
    )
    (net (code "40") (name "/EX4") (class "Default")
      (node (ref "R13") (pin "2") (pinfunction "2_2") (pintype "passive"))
      (node (ref "U2") (pin "1") (pinfunction "X4_1") (pintype "bidirectional"))
      (node (ref "U4") (pin "7") (pinfunction "A5_7") (pintype "bidirectional"))
    )
    (net (code "41") (name "/EX5") (class "Default")
      (node (ref "R14") (pin "2") (pinfunction "2_2") (pintype "passive"))
      (node (ref "U2") (pin "5") (pinfunction "X5_5") (pintype "bidirectional"))
      (node (ref "U4") (pin "8") (pinfunction "A6_8") (pintype "bidirectional"))
    )
    (net (code "42") (name "/EX6") (class "Default")
      (node (ref "R15") (pin "2") (pinfunction "2_2") (pintype "passive"))
      (node (ref "U2") (pin "2") (pinfunction "X6_2") (pintype "bidirectional"))
      (node (ref "U4") (pin "9") (pinfunction "A7_9") (pintype "bidirectional"))
    )
    (net (code "43") (name "/EX7") (class "Default")
      (node (ref "R16") (pin "2") (pinfunction "2_2") (pintype "passive"))
      (node (ref "U2") (pin "4") (pinfunction "X7_4") (pintype "bidirectional"))
      (node (ref "U4") (pin "10") (pinfunction "A8_10") (pintype "bidirectional"))
    )
    (net (code "44") (name "/EX_0") (class "Default")
      (node (ref "J5") (pin "7") (pinfunction "7_7") (pintype "passive"))
      (node (ref "U4") (pin "21") (pinfunction "B1_21") (pintype "bidirectional"))
    )
    (net (code "45") (name "/EX_1") (class "Default")
      (node (ref "J6") (pin "7") (pinfunction "7_7") (pintype "passive"))
      (node (ref "U4") (pin "20") (pinfunction "B2_20") (pintype "bidirectional"))
    )
    (net (code "46") (name "/EX_2") (class "Default")
      (node (ref "J7") (pin "7") (pinfunction "7_7") (pintype "passive"))
      (node (ref "U4") (pin "19") (pinfunction "B3_19") (pintype "bidirectional"))
    )
    (net (code "47") (name "/EX_3") (class "Default")
      (node (ref "J8") (pin "7") (pinfunction "7_7") (pintype "passive"))
      (node (ref "U4") (pin "18") (pinfunction "B4_18") (pintype "bidirectional"))
    )
    (net (code "48") (name "/EX_4") (class "Default")
      (node (ref "J9") (pin "7") (pinfunction "7_7") (pintype "passive"))
      (node (ref "U4") (pin "17") (pinfunction "B5_17") (pintype "bidirectional"))
    )
    (net (code "49") (name "/EX_5") (class "Default")
      (node (ref "J10") (pin "7") (pinfunction "7_7") (pintype "passive"))
      (node (ref "U4") (pin "16") (pinfunction "B6_16") (pintype "bidirectional"))
    )
    (net (code "50") (name "/EX_6") (class "Default")
      (node (ref "J11") (pin "7") (pinfunction "7_7") (pintype "passive"))
      (node (ref "U4") (pin "15") (pinfunction "B7_15") (pintype "bidirectional"))
    )
    (net (code "51") (name "/EX_7") (class "Default")
      (node (ref "J12") (pin "7") (pinfunction "7_7") (pintype "passive"))
      (node (ref "U4") (pin "14") (pinfunction "B8_14") (pintype "bidirectional"))
    )
    (net (code "52") (name "/EX_8") (class "Default")
      (node (ref "IC1") (pin "61") (pinfunction "PB8_61") (pintype "bidirectional"))
      (node (ref "J13") (pin "7") (pinfunction "7_7") (pintype "passive"))
      (node (ref "R4") (pin "2") (pinfunction "2_2") (pintype "passive"))
    )
    (net (code "53") (name "/EX_9") (class "Default")
      (node (ref "IC1") (pin "62") (pinfunction "PB9_62") (pintype "bidirectional"))
      (node (ref "J14") (pin "7") (pinfunction "7_7") (pintype "passive"))
      (node (ref "R19") (pin "2") (pinfunction "2_2") (pintype "passive"))
    )
    (net (code "54") (name "/GD_1") (class "Default")
      (node (ref "IC1") (pin "8") (pinfunction "PC0_8") (pintype "bidirectional"))
      (node (ref "J15") (pin "2") (pinfunction "2_2") (pintype "passive"))
    )
    (net (code "55") (name "/GD_2") (class "Default")
      (node (ref "IC1") (pin "9") (pinfunction "PC1_9") (pintype "bidirectional"))
      (node (ref "J17") (pin "2") (pinfunction "2_2") (pintype "passive"))
    )
    (net (code "56") (name "/GD_3") (class "Default")
      (node (ref "IC1") (pin "10") (pinfunction "PC2_10") (pintype "bidirectional"))
      (node (ref "J16") (pin "2") (pinfunction "2_2") (pintype "passive"))
    )
    (net (code "57") (name "/GD_4") (class "Default")
      (node (ref "IC1") (pin "11") (pinfunction "PC3_11") (pintype "bidirectional"))
      (node (ref "J18") (pin "2") (pinfunction "2_2") (pintype "passive"))
    )
    (net (code "58") (name "/NRST") (class "Default")
      (node (ref "C5") (pin "2") (pinfunction "2_2") (pintype "passive"))
      (node (ref "IC1") (pin "7") (pinfunction "NRST_7") (pintype "bidirectional"))
      (node (ref "R2") (pin "1") (pinfunction "1_1") (pintype "passive"))
      (node (ref "S1") (pin "1") (pinfunction "1_1") (pintype "passive"))
    )
    (net (code "59") (name "/PB12") (class "Default")
      (node (ref "IC1") (pin "33") (pinfunction "PB12_33") (pintype "bidirectional"))
      (node (ref "R6") (pin "1") (pinfunction "1_1") (pintype "passive"))
    )
    (net (code "60") (name "/POWER") (class "Default")
      (node (ref "C10") (pin "1") (pinfunction "1_1") (pintype "passive"))
      (node (ref "C11") (pin "2") (pinfunction "2_2") (pintype "passive"))
      (node (ref "Charge") (pin "1") (pinfunction "1_1") (pintype "passive"))
      (node (ref "U1") (pin "4") (pinfunction "VCC_4") (pintype "passive"))
      (node (ref "USB1") (pin "2") (pinfunction "2_2") (pintype "passive"))
    )
    (net (code "61") (name "/RXD1") (class "Default")
      (node (ref "IC1") (pin "29") (pinfunction "PB10_29") (pintype "bidirectional"))
      (node (ref "J2") (pin "4") (pinfunction "4_4") (pintype "passive"))
    )
    (net (code "62") (name "/SCL") (class "Default")
      (node (ref "IC1") (pin "58") (pinfunction "PB6_58") (pintype "bidirectional"))
      (node (ref "J3") (pin "2") (pinfunction "2_2") (pintype "passive"))
    )
    (net (code "63") (name "/SDA") (class "Default")
      (node (ref "IC1") (pin "59") (pinfunction "PB7_59") (pintype "bidirectional"))
      (node (ref "J3") (pin "1") (pinfunction "1_1") (pintype "passive"))
    )
    (net (code "64") (name "/TXD1") (class "Default")
      (node (ref "IC1") (pin "30") (pinfunction "PB11_30") (pintype "bidirectional"))
      (node (ref "J2") (pin "3") (pinfunction "3_3") (pintype "passive"))
    )
    (net (code "65") (name "/XTAL_A") (class "Default")
      (node (ref "C6") (pin "2") (pinfunction "2_2") (pintype "passive"))
      (node (ref "IC1") (pin "5") (pinfunction "OSC_IN/PD0_5") (pintype "input"))
      (node (ref "R3") (pin "1") (pinfunction "1_1") (pintype "passive"))
      (node (ref "Y1") (pin "1") (pinfunction "OSC1_1") (pintype "passive"))
    )
    (net (code "66") (name "/XTAL_B") (class "Default")
      (node (ref "C7") (pin "2") (pinfunction "2_2") (pintype "passive"))
      (node (ref "IC1") (pin "6") (pinfunction "OSC_OUT/PD1_6") (pintype "output"))
      (node (ref "R3") (pin "2") (pinfunction "2_2") (pintype "passive"))
      (node (ref "Y1") (pin "2") (pinfunction "OSC2_2") (pintype "passive"))
    )
    (net (code "67") (name "/XTAL_C") (class "Default")
      (node (ref "C8") (pin "2") (pinfunction "2_2") (pintype "passive"))
      (node (ref "IC1") (pin "3") (pinfunction "PC14-OSC32_IN_3") (pintype "bidirectional"))
      (node (ref "Y2") (pin "1") (pinfunction "OSC1_1") (pintype "passive"))
    )
    (net (code "68") (name "/XTAL_D") (class "Default")
      (node (ref "C9") (pin "2") (pinfunction "2_2") (pintype "passive"))
      (node (ref "IC1") (pin "4") (pinfunction "PC15-OSC32_OUT_4") (pintype "bidirectional"))
      (node (ref "Y2") (pin "2") (pinfunction "OSC2_2") (pintype "passive"))
    )
    (net (code "69") (name "GND") (class "Default")
      (node (ref "C1") (pin "1") (pinfunction "1_1") (pintype "passive"))
      (node (ref "C10") (pin "2") (pinfunction "2_2") (pintype "passive"))
      (node (ref "C11") (pin "1") (pinfunction "1_1") (pintype "passive"))
      (node (ref "C12") (pin "1") (pinfunction "1_1") (pintype "passive"))
      (node (ref "C13") (pin "1") (pinfunction "1_1") (pintype "passive"))
      (node (ref "C14") (pin "1") (pinfunction "1_1") (pintype "passive"))
      (node (ref "C15") (pin "1") (pinfunction "1_1") (pintype "passive"))
      (node (ref "C16") (pin "1") (pinfunction "1_1") (pintype "passive"))
      (node (ref "C17") (pin "1") (pinfunction "1_1") (pintype "passive"))
      (node (ref "C18") (pin "2") (pinfunction "2_2") (pintype "passive"))
      (node (ref "C19") (pin "2") (pinfunction "2_2") (pintype "passive"))
      (node (ref "C2") (pin "1") (pinfunction "1_1") (pintype "passive"))
      (node (ref "C20") (pin "2") (pinfunction "2_2") (pintype "passive"))
      (node (ref "C21") (pin "2") (pinfunction "2_2") (pintype "passive"))
      (node (ref "C22") (pin "2") (pinfunction "2_2") (pintype "passive"))
      (node (ref "C23") (pin "2") (pinfunction "2_2") (pintype "passive"))
      (node (ref "C3") (pin "1") (pinfunction "1_1") (pintype "passive"))
      (node (ref "C4") (pin "1") (pinfunction "1_1") (pintype "passive"))
      (node (ref "C5") (pin "1") (pinfunction "1_1") (pintype "passive"))
      (node (ref "C6") (pin "1") (pinfunction "1_1") (pintype "passive"))
      (node (ref "C7") (pin "1") (pinfunction "1_1") (pintype "passive"))
      (node (ref "C8") (pin "1") (pinfunction "1_1") (pintype "passive"))
      (node (ref "C9") (pin "1") (pinfunction "1_1") (pintype "passive"))
      (node (ref "IC1") (pin "12") (pinfunction "VSSA_12") (pintype "power_in"))
      (node (ref "IC1") (pin "18") (pinfunction "VSS_4_18") (pintype "power_in"))
      (node (ref "IC1") (pin "31") (pinfunction "VSS_1_31") (pintype "power_in"))
      (node (ref "IC1") (pin "47") (pinfunction "VSS_2_47") (pintype "power_in"))
      (node (ref "IC1") (pin "63") (pinfunction "VSS_3_63") (pintype "power_in"))
      (node (ref "IC2") (pin "2") (pinfunction "GND_2") (pintype "passive"))
      (node (ref "J1") (pin "1") (pinfunction "1_1") (pintype "passive"))
      (node (ref "J10") (pin "4") (pinfunction "4_4") (pintype "passive"))
      (node (ref "J11") (pin "4") (pinfunction "4_4") (pintype "passive"))
      (node (ref "J12") (pin "4") (pinfunction "4_4") (pintype "passive"))
      (node (ref "J13") (pin "4") (pinfunction "4_4") (pintype "passive"))
      (node (ref "J14") (pin "4") (pinfunction "4_4") (pintype "passive"))
      (node (ref "J15") (pin "1") (pinfunction "1_1") (pintype "passive"))
      (node (ref "J16") (pin "1") (pinfunction "1_1") (pintype "passive"))
      (node (ref "J17") (pin "1") (pinfunction "1_1") (pintype "passive"))
      (node (ref "J18") (pin "1") (pinfunction "1_1") (pintype "passive"))
      (node (ref "J2") (pin "2") (pinfunction "2_2") (pintype "passive"))
      (node (ref "J3") (pin "3") (pinfunction "3_3") (pintype "passive"))
      (node (ref "J4") (pin "2") (pinfunction "2_2") (pintype "passive"))
      (node (ref "J5") (pin "4") (pinfunction "4_4") (pintype "passive"))
      (node (ref "J6") (pin "4") (pinfunction "4_4") (pintype "passive"))
      (node (ref "J7") (pin "4") (pinfunction "4_4") (pintype "passive"))
      (node (ref "J8") (pin "4") (pinfunction "4_4") (pintype "passive"))
      (node (ref "J9") (pin "4") (pinfunction "4_4") (pintype "passive"))
      (node (ref "R1") (pin "2") (pinfunction "2_2") (pintype "passive"))
      (node (ref "R10") (pin "1") (pinfunction "1_1") (pintype "passive"))
      (node (ref "R11") (pin "1") (pinfunction "1_1") (pintype "passive"))
      (node (ref "R12") (pin "1") (pinfunction "1_1") (pintype "passive"))
      (node (ref "R13") (pin "1") (pinfunction "1_1") (pintype "passive"))
      (node (ref "R14") (pin "1") (pinfunction "1_1") (pintype "passive"))
      (node (ref "R15") (pin "1") (pinfunction "1_1") (pintype "passive"))
      (node (ref "R16") (pin "1") (pinfunction "1_1") (pintype "passive"))
      (node (ref "R18") (pin "2") (pinfunction "2_2") (pintype "passive"))
      (node (ref "R19") (pin "1") (pinfunction "1_1") (pintype "passive"))
      (node (ref "R20") (pin "1") (pinfunction "1_1") (pintype "passive"))
      (node (ref "R4") (pin "1") (pinfunction "1_1") (pintype "passive"))
      (node (ref "R5") (pin "1") (pinfunction "1_1") (pintype "passive"))
      (node (ref "R7") (pin "2") (pinfunction "2_2") (pintype "passive"))
      (node (ref "R9") (pin "1") (pinfunction "1_1") (pintype "passive"))
      (node (ref "S1") (pin "2") (pinfunction "2_2") (pintype "passive"))
      (node (ref "U1") (pin "2") (pinfunction "GND_2") (pintype "passive"))
      (node (ref "U2") (pin "6") (pinfunction "~{EN}_6") (pintype "input"))
      (node (ref "U2") (pin "7") (pinfunction "VEE_7") (pintype "power_in"))
      (node (ref "U2") (pin "8") (pinfunction "GND_8") (pintype "power_in"))
      (node (ref "U3") (pin "2") (pinfunction "GND_2") (pintype "passive"))
      (node (ref "U4") (pin "11") (pinfunction "GND_11") (pintype "power_in"))
      (node (ref "U4") (pin "12") (pinfunction "GND_12") (pintype "power_in"))
      (node (ref "U4") (pin "13") (pinfunction "GND_13") (pintype "power_in"))
      (node (ref "U4") (pin "22") (pinfunction "~{OE}_22") (pintype "input"))
      (node (ref "U5") (pin "11") (pinfunction "GND_11") (pintype "power_in"))
      (node (ref "U5") (pin "12") (pinfunction "GND_12") (pintype "power_in"))
      (node (ref "U5") (pin "13") (pinfunction "GND_13") (pintype "power_in"))
      (node (ref "U5") (pin "22") (pinfunction "~{OE}_22") (pintype "input"))
      (node (ref "U6") (pin "11") (pinfunction "GND_11") (pintype "power_in"))
      (node (ref "U6") (pin "12") (pinfunction "GND_12") (pintype "power_in"))
      (node (ref "U6") (pin "13") (pinfunction "GND_13") (pintype "power_in"))
      (node (ref "U6") (pin "22") (pinfunction "~{OE}_22") (pintype "input"))
      (node (ref "USB1") (pin "1") (pinfunction "1_1") (pintype "passive"))
    )
    (net (code "70") (name "Net-(Charge-Pad2)") (class "Default")
      (node (ref "Charge") (pin "2") (pinfunction "2_2") (pintype "passive"))
      (node (ref "R8") (pin "2") (pinfunction "2_2") (pintype "passive"))
    )
    (net (code "71") (name "Net-(IC1-PA13{slash}JTMS{slash}SWDIO)") (class "Default")
      (node (ref "IC1") (pin "46") (pinfunction "PA13/JTMS/SWDIO_46") (pintype "bidirectional"))
      (node (ref "J1") (pin "3") (pinfunction "3_3") (pintype "passive"))
    )
    (net (code "72") (name "Net-(IC1-PA14{slash}JTCK{slash}SWCLK)") (class "Default")
      (node (ref "IC1") (pin "49") (pinfunction "PA14/JTCK/SWCLK_49") (pintype "bidirectional"))
      (node (ref "J1") (pin "2") (pinfunction "2_2") (pintype "passive"))
    )
    (net (code "73") (name "Net-(IC2-BYP)") (class "Default")
      (node (ref "C13") (pin "2") (pinfunction "2_2") (pintype "passive"))
      (node (ref "IC2") (pin "4") (pinfunction "BYP_4") (pintype "passive"))
    )
    (net (code "74") (name "Net-(Power-Pad2)") (class "Default")
      (node (ref "Power") (pin "2") (pinfunction "2_2") (pintype "passive"))
      (node (ref "R5") (pin "2") (pinfunction "2_2") (pintype "passive"))
    )
    (net (code "75") (name "Net-(R6-Pad2)") (class "Default")
      (node (ref "R6") (pin "2") (pinfunction "2_2") (pintype "passive"))
      (node (ref "Statu") (pin "2") (pinfunction "2_2") (pintype "passive"))
    )
    (net (code "76") (name "Net-(U1-PROG)") (class "Default")
      (node (ref "R7") (pin "1") (pinfunction "1_1") (pintype "passive"))
      (node (ref "U1") (pin "5") (pinfunction "PROG_5") (pintype "passive"))
    )
    (net (code "77") (name "Net-(U1-~{CHRG})") (class "Default")
      (node (ref "R8") (pin "1") (pinfunction "1_1") (pintype "passive"))
      (node (ref "U1") (pin "1") (pinfunction "~{CHRG}_1") (pintype "passive"))
    )
    (net (code "78") (name "Net-(U3-FB)") (class "Default")
      (node (ref "R17") (pin "2") (pinfunction "2_2") (pintype "passive"))
      (node (ref "R18") (pin "1") (pinfunction "1_1") (pintype "passive"))
      (node (ref "U3") (pin "3") (pinfunction "FB_3") (pintype "passive"))
    )
    (net (code "79") (name "Net-(U3-LX)") (class "Default")
      (node (ref "L1") (pin "2") (pinfunction "2_2") (pintype "passive"))
      (node (ref "U3") (pin "1") (pinfunction "LX_1") (pintype "passive"))
    )
    (net (code "80") (name "VCC3.3") (class "Default")
      (node (ref "C1") (pin "2") (pinfunction "2_2") (pintype "passive"))
      (node (ref "C12") (pin "2") (pinfunction "2_2") (pintype "passive"))
      (node (ref "C18") (pin "1") (pinfunction "1_1") (pintype "passive"))
      (node (ref "C2") (pin "2") (pinfunction "2_2") (pintype "passive"))
      (node (ref "C20") (pin "1") (pinfunction "1_1") (pintype "passive"))
      (node (ref "C22") (pin "1") (pinfunction "1_1") (pintype "passive"))
      (node (ref "C3") (pin "2") (pinfunction "2_2") (pintype "passive"))
      (node (ref "C4") (pin "2") (pinfunction "2_2") (pintype "passive"))
      (node (ref "IC1") (pin "1") (pinfunction "VBAT_1") (pintype "power_in"))
      (node (ref "IC1") (pin "13") (pinfunction "VDDA_13") (pintype "power_in"))
      (node (ref "IC1") (pin "19") (pinfunction "VDD_4_19") (pintype "power_in"))
      (node (ref "IC1") (pin "32") (pinfunction "VDD_1_32") (pintype "power_in"))
      (node (ref "IC1") (pin "48") (pinfunction "VDD_2_48") (pintype "power_in"))
      (node (ref "IC1") (pin "64") (pinfunction "VDD_3_64") (pintype "power_in"))
      (node (ref "IC2") (pin "5") (pinfunction "OUT_5") (pintype "passive"))
      (node (ref "J1") (pin "4") (pinfunction "4_4") (pintype "passive"))
      (node (ref "J3") (pin "4") (pinfunction "4_4") (pintype "passive"))
      (node (ref "Power") (pin "1") (pinfunction "1_1") (pintype "passive"))
      (node (ref "R2") (pin "2") (pinfunction "2_2") (pintype "passive"))
      (node (ref "Statu") (pin "1") (pinfunction "1_1") (pintype "passive"))
      (node (ref "U4") (pin "1") (pinfunction "VccA_1") (pintype "power_in"))
      (node (ref "U4") (pin "2") (pinfunction "DIR_2") (pintype "input"))
      (node (ref "U5") (pin "1") (pinfunction "VccA_1") (pintype "power_in"))
      (node (ref "U5") (pin "2") (pinfunction "DIR_2") (pintype "input"))
      (node (ref "U6") (pin "1") (pinfunction "VccA_1") (pintype "power_in"))
      (node (ref "U6") (pin "2") (pinfunction "DIR_2") (pintype "input"))
    )
    (net (code "81") (name "unconnected-(IC1-PA12-Pad45)") (class "Default")
      (node (ref "IC1") (pin "45") (pinfunction "PA12_45") (pintype "bidirectional+no_connect"))
    )
    (net (code "82") (name "unconnected-(IC1-PA15{slash}JTDI-Pad50)") (class "Default")
      (node (ref "IC1") (pin "50") (pinfunction "PA15/JTDI_50") (pintype "bidirectional+no_connect"))
    )
    (net (code "83") (name "unconnected-(IC1-PB13-Pad34)") (class "Default")
      (node (ref "IC1") (pin "34") (pinfunction "PB13_34") (pintype "bidirectional+no_connect"))
    )
    (net (code "84") (name "unconnected-(IC1-PB14-Pad35)") (class "Default")
      (node (ref "IC1") (pin "35") (pinfunction "PB14_35") (pintype "bidirectional+no_connect"))
    )
    (net (code "85") (name "unconnected-(IC1-PB15-Pad36)") (class "Default")
      (node (ref "IC1") (pin "36") (pinfunction "PB15_36") (pintype "bidirectional+no_connect"))
    )
    (net (code "86") (name "unconnected-(IC1-PC4-Pad24)") (class "Default")
      (node (ref "IC1") (pin "24") (pinfunction "PC4_24") (pintype "bidirectional+no_connect"))
    )
    (net (code "87") (name "unconnected-(IC1-PC5-Pad25)") (class "Default")
      (node (ref "IC1") (pin "25") (pinfunction "PC5_25") (pintype "bidirectional+no_connect"))
    )
    (net (code "88") (name "unconnected-(IC1-PC6-Pad37)") (class "Default")
      (node (ref "IC1") (pin "37") (pinfunction "PC6_37") (pintype "bidirectional+no_connect"))
    )
    (net (code "89") (name "unconnected-(IC1-PC7-Pad38)") (class "Default")
      (node (ref "IC1") (pin "38") (pinfunction "PC7_38") (pintype "bidirectional+no_connect"))
    )
    (net (code "90") (name "unconnected-(IC1-PC8-Pad39)") (class "Default")
      (node (ref "IC1") (pin "39") (pinfunction "PC8_39") (pintype "bidirectional+no_connect"))
    )
    (net (code "91") (name "unconnected-(IC1-PC9-Pad40)") (class "Default")
      (node (ref "IC1") (pin "40") (pinfunction "PC9_40") (pintype "bidirectional+no_connect"))
    )
    (net (code "92") (name "unconnected-(IC1-PC10-Pad51)") (class "Default")
      (node (ref "IC1") (pin "51") (pinfunction "PC10_51") (pintype "bidirectional+no_connect"))
    )
    (net (code "93") (name "unconnected-(IC1-PC11-Pad52)") (class "Default")
      (node (ref "IC1") (pin "52") (pinfunction "PC11_52") (pintype "bidirectional+no_connect"))
    )
    (net (code "94") (name "unconnected-(IC1-PC12-Pad53)") (class "Default")
      (node (ref "IC1") (pin "53") (pinfunction "PC12_53") (pintype "bidirectional+no_connect"))
    )
    (net (code "95") (name "unconnected-(IC1-PC13-TAMPER-RTC-Pad2)") (class "Default")
      (node (ref "IC1") (pin "2") (pinfunction "PC13-TAMPER-RTC_2") (pintype "bidirectional+no_connect"))
    )
    (net (code "96") (name "unconnected-(IC1-PD2-Pad54)") (class "Default")
      (node (ref "IC1") (pin "54") (pinfunction "PD2_54") (pintype "bidirectional"))
    )
    (net (code "97") (name "unconnected-(K1-I{slash}O1-Pad1)") (class "Default")
      (node (ref "K1") (pin "1") (pinfunction "I/O1_1") (pintype "passive+no_connect"))
    )
    (net (code "98") (name "unconnected-(K1-I{slash}O2-Pad4)") (class "Default")
      (node (ref "K1") (pin "4") (pinfunction "I/O2_4") (pintype "passive+no_connect"))
    )
    (net (code "99") (name "unconnected-(K1-I{slash}O2-Pad6)") (class "Default")
      (node (ref "K1") (pin "6") (pinfunction "I/O2_6") (pintype "passive+no_connect"))
    )
    (net (code "100") (name "unconnected-(K1-TAP2-Pad5)") (class "Default")
      (node (ref "K1") (pin "5") (pinfunction "TAP2_5") (pintype "passive+no_connect"))
    )
    (net (code "101") (name "unconnected-(U6-A8-Pad10)") (class "Default")
      (node (ref "U6") (pin "10") (pinfunction "A8_10") (pintype "bidirectional+no_connect"))
    )
    (net (code "102") (name "unconnected-(U6-B8-Pad14)") (class "Default")
      (node (ref "U6") (pin "14") (pinfunction "B8_14") (pintype "bidirectional+no_connect"))
    )
  )
)
